# fp_binding_posts.net
KiCad netlist of a schematic drawn in EAGLE
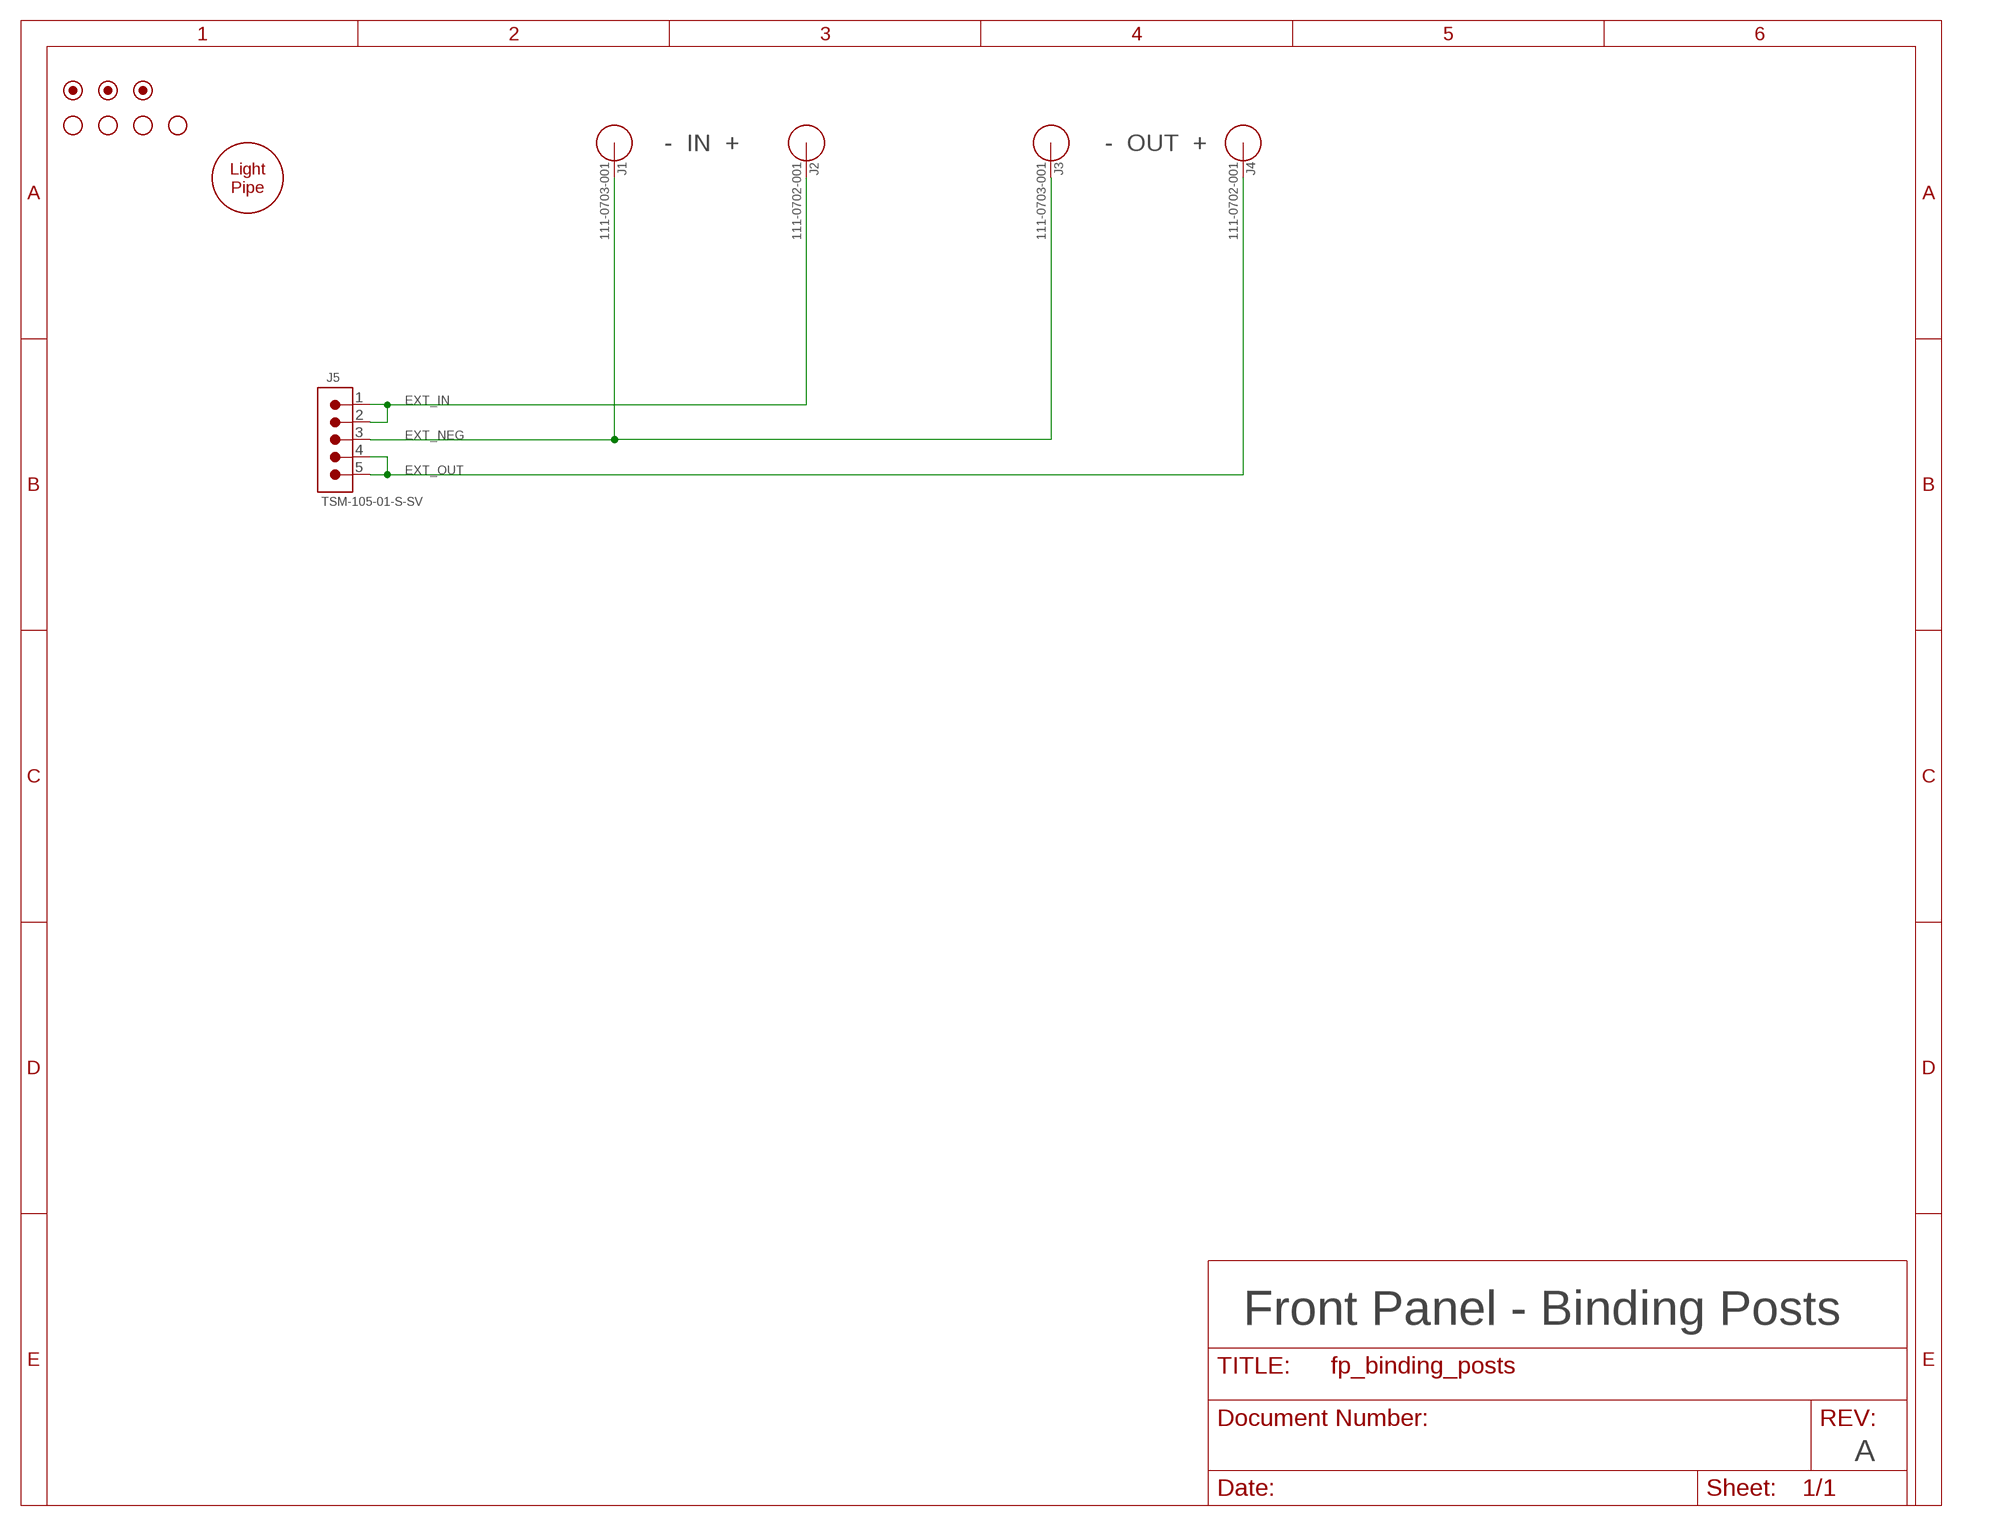
[diagram p0: schematic, sheet 1]

(export (version "E")
  (design (tool "Eeschema 10.0.6"))
  (components
    (comp (ref "FUD1")
      (value "FIDUCIAL_1MM")
      (footprint "eagle-import:FIDUCIAL_1MM_2MM")
      (libsource (lib "eagle-import") (part "FIDUCIAL_1MM"))
    )
    (comp (ref "FUD2")
      (value "FIDUCIAL_1MM")
      (footprint "eagle-import:FIDUCIAL_1MM_2MM")
      (libsource (lib "eagle-import") (part "FIDUCIAL_1MM"))
    )
    (comp (ref "FUD3")
      (value "FIDUCIAL_1MM")
      (footprint "eagle-import:FIDUCIAL_1MM_2MM")
      (libsource (lib "eagle-import") (part "FIDUCIAL_1MM"))
    )
    (comp (ref "H1")
      (value "51513020125F")
      (footprint "eagle-import:LP_3MM")
      (fields (field (name "MPN") "51513020125F"))
      (libsource (lib "eagle-import") (part "LIGHT_PIPE_PANEL_3MM"))
    )
    (comp (ref "H2")
      (value "HOLE_#6")
      (footprint "eagle-import:HOLE_3.5MM")
      (libsource (lib "eagle-import") (part "HOLE_#6"))
    )
    (comp (ref "H3")
      (value "HOLE_#6")
      (footprint "eagle-import:HOLE_3.5MM")
      (libsource (lib "eagle-import") (part "HOLE_#6"))
    )
    (comp (ref "H4")
      (value "HOLE_#6")
      (footprint "eagle-import:HOLE_3.5MM")
      (libsource (lib "eagle-import") (part "HOLE_#6"))
    )
    (comp (ref "H5")
      (value "HOLE_#6")
      (footprint "eagle-import:HOLE_3.5MM")
      (libsource (lib "eagle-import") (part "HOLE_#6"))
    )
    (comp (ref "J1")
      (value "111-0703-001")
      (footprint "eagle-import:BINDING_POST_6")
      (libsource (lib "eagle-import") (part "BINDING_POST_6"))
    )
    (comp (ref "J2")
      (value "111-0702-001")
      (footprint "eagle-import:BINDING_POST_6")
      (libsource (lib "eagle-import") (part "BINDING_POST_6"))
    )
    (comp (ref "J3")
      (value "111-0703-001")
      (footprint "eagle-import:BINDING_POST_6")
      (libsource (lib "eagle-import") (part "BINDING_POST_6"))
    )
    (comp (ref "J4")
      (value "111-0702-001")
      (footprint "eagle-import:BINDING_POST_6")
      (libsource (lib "eagle-import") (part "BINDING_POST_6"))
    )
    (comp (ref "J5")
      (value "TSM-105-01-S-SV")
      (footprint "eagle-import:CONN_0.1_5X1_MS")
      (libsource (lib "eagle-import") (part "CONN_0.1_5X1_MS"))
    )
  )
  (nets
    (net (code "1") (name "/EXT_IN") (class "Default")
      (node (ref "J2") (pin "1") (pinfunction "1_1") (pintype "bidirectional"))
      (node (ref "J5") (pin "1") (pinfunction "1_1") (pintype "bidirectional"))
      (node (ref "J5") (pin "2") (pinfunction "2_2") (pintype "bidirectional"))
    )
    (net (code "2") (name "/EXT_NEG") (class "Default")
      (node (ref "J1") (pin "1") (pinfunction "1_1") (pintype "bidirectional"))
      (node (ref "J3") (pin "1") (pinfunction "1_1") (pintype "bidirectional"))
      (node (ref "J5") (pin "3") (pinfunction "3_3") (pintype "bidirectional"))
    )
    (net (code "3") (name "/EXT_OUT") (class "Default")
      (node (ref "J4") (pin "1") (pinfunction "1_1") (pintype "bidirectional"))
      (node (ref "J5") (pin "4") (pinfunction "4_4") (pintype "bidirectional"))
      (node (ref "J5") (pin "5") (pinfunction "5_5") (pintype "bidirectional"))
    )
  )
)
